# SlimTx.net
KiCad netlist of a schematic drawn in Altium Designer
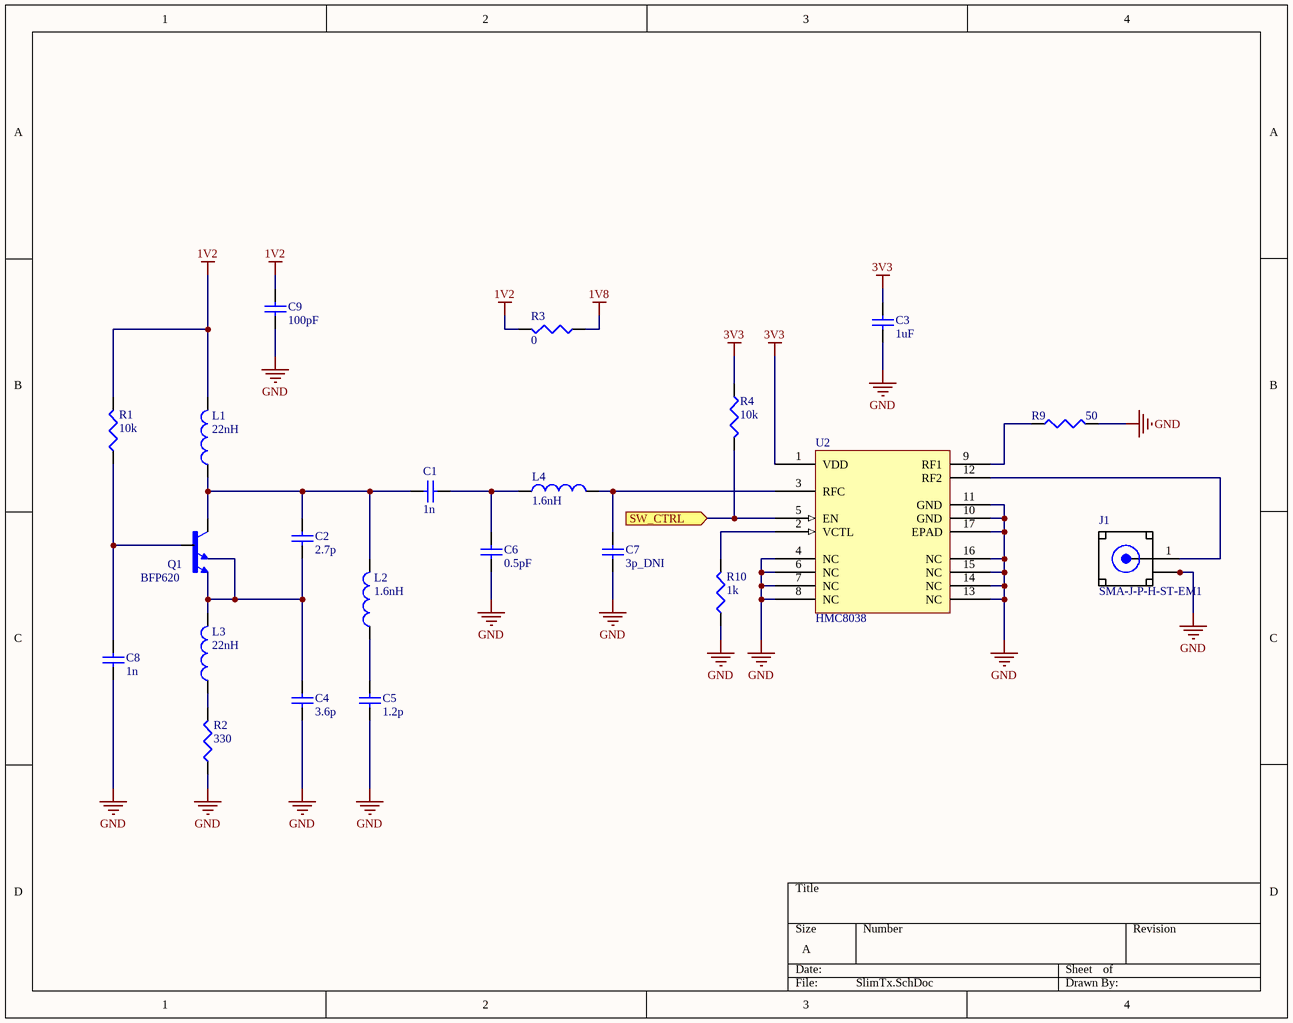
[diagram p0: SlimTx.SchDoc]

(export (version "E")
  (design (tool "Eeschema 10.0.6"))
  (components
    (comp (ref "C1")
      (value "1n")
      (footprint "SMD-0603")
      (description "Ceramic Capacitor 0603")
      (libsource (lib "LCR") (part "CAP0603"))
    )
    (comp (ref "C2")
      (value "2.7p")
      (footprint "SMD-0603")
      (description "Ceramic Capacitor 0603")
      (libsource (lib "LCR") (part "CAP0603"))
    )
    (comp (ref "C3")
      (value "1uF")
      (footprint "SMD-0603")
      (description "Ceramic Capacitor 0603")
      (libsource (lib "LCR") (part "CAP0603"))
    )
    (comp (ref "C4")
      (value "3.6p")
      (footprint "SMD-0603")
      (description "Ceramic Capacitor 0603")
      (libsource (lib "LCR") (part "CAP0603"))
    )
    (comp (ref "C5")
      (value "1.2p")
      (footprint "SMD-0603")
      (description "Ceramic Capacitor 0603")
      (libsource (lib "LCR") (part "CAP0603"))
    )
    (comp (ref "C6")
      (value "0.5pF")
      (footprint "SMD-0603")
      (description "Ceramic Capacitor 0603")
      (libsource (lib "LCR") (part "CAP0603"))
    )
    (comp (ref "C7")
      (value "3p_DNI")
      (footprint "SMD-0603")
      (description "Ceramic Capacitor 0603")
      (libsource (lib "LCR") (part "CAP0603"))
    )
    (comp (ref "C8")
      (value "1n")
      (footprint "SMD-0603")
      (description "Ceramic Capacitor 0603")
      (libsource (lib "LCR") (part "CAP0603"))
    )
    (comp (ref "C9")
      (value "100pF")
      (footprint "SMD-0603")
      (description "Ceramic Capacitor 0603")
      (libsource (lib "LCR") (part "CAP0603"))
    )
    (comp (ref "J1")
      (value "SMA-J-P-H-ST-EM1")
      (footprint "SMA-J-P-H-ST-EM1")
      (description "Connector SMA F 50Ohm Solder ST Edge Mount Gold Over Nickel Tray")
      (fields (field (name "MF") "Samtec"))
      (libsource (lib "Connectors") (part "SMA-J-P-H-ST-EM1"))
    )
    (comp (ref "L1")
      (value "22nH")
      (footprint "SMD-0603")
      (description "Inductor 0603")
      (libsource (lib "LCR") (part "L0603"))
    )
    (comp (ref "L2")
      (value "1.6nH")
      (footprint "SMD-0603")
      (description "Inductor 0603")
      (libsource (lib "LCR") (part "L0603"))
    )
    (comp (ref "L3")
      (value "22nH")
      (footprint "SMD-0603")
      (description "Inductor 0603")
      (libsource (lib "LCR") (part "L0603"))
    )
    (comp (ref "L4")
      (value "1.6nH")
      (footprint "SMD-0603")
      (description "Inductor 0603")
      (libsource (lib "LCR") (part "L0603"))
    )
    (comp (ref "Q1")
      (value "BFP620")
      (footprint "SOT343")
      (description "Trans RF BJT NPN 2.3V 0.08A 185mW Automotive 4-Pin(3+Tab) SOT-343 T/R")
      (fields (field (name "MF") "Infineon Technologies"))
      (libsource (lib "BFP620") (part "BFP620"))
    )
    (comp (ref "R1")
      (value "10k")
      (footprint "SMD-0603")
      (description "Resistor-0603")
      (libsource (lib "LCR") (part "RES0603"))
    )
    (comp (ref "R2")
      (value "330")
      (footprint "SMD-0603")
      (description "Resistor-0603")
      (libsource (lib "LCR") (part "RES0603"))
    )
    (comp (ref "R3")
      (value "0")
      (footprint "SMD-0603")
      (description "Resistor-0603")
      (libsource (lib "LCR") (part "RES0603"))
    )
    (comp (ref "R4")
      (value "10k")
      (footprint "SMD-0603")
      (description "Resistor-0603")
      (libsource (lib "LCR") (part "RES0603"))
    )
    (comp (ref "R9")
      (value "50")
      (footprint "SMD-0603")
      (description "Resistor-0603")
      (libsource (lib "LCR") (part "RES0603"))
    )
    (comp (ref "R10")
      (value "1k")
      (footprint "SMD-0603")
      (description "Resistor-0603")
      (libsource (lib "LCR") (part "RES0603"))
    )
    (comp (ref "U2")
      (value "HMC8038")
      (footprint "PQFN127P600-8N LFCSP-17")
      (description "High Isolation, Silicon SPDT, Nonreflective Switch, 0.1 GHz to 6.0 GHz")
      (libsource (lib "HMC8038") (part "HMC8038"))
    )
  )
  (nets
    (net (code "1") (name "/SW_CTRL") (class "Default")
      (node (ref "R4") (pin "2") (pinfunction "2_2") (pintype "passive"))
      (node (ref "U2") (pin "5") (pinfunction "EN_5") (pintype "input"))
    )
    (net (code "2") (name "1V2") (class "Default")
      (node (ref "C9") (pin "2") (pinfunction "2_2") (pintype "passive"))
      (node (ref "L1") (pin "2") (pinfunction "2_2") (pintype "passive"))
      (node (ref "R1") (pin "2") (pinfunction "2_2") (pintype "passive"))
      (node (ref "R3") (pin "2") (pinfunction "2_2") (pintype "passive"))
    )
    (net (code "3") (name "1V8") (class "Default")
      (node (ref "R3") (pin "1") (pinfunction "1_1") (pintype "passive"))
    )
    (net (code "4") (name "3V3") (class "Default")
      (node (ref "C3") (pin "2") (pinfunction "2_2") (pintype "passive"))
      (node (ref "R4") (pin "1") (pinfunction "1_1") (pintype "passive"))
      (node (ref "U2") (pin "1") (pinfunction "VDD_1") (pintype "power_in"))
    )
    (net (code "5") (name "GND") (class "Default")
      (node (ref "C3") (pin "1") (pinfunction "1_1") (pintype "passive"))
      (node (ref "C4") (pin "1") (pinfunction "1_1") (pintype "passive"))
      (node (ref "C5") (pin "1") (pinfunction "1_1") (pintype "passive"))
      (node (ref "C6") (pin "1") (pinfunction "1_1") (pintype "passive"))
      (node (ref "C7") (pin "1") (pinfunction "1_1") (pintype "passive"))
      (node (ref "C8") (pin "1") (pinfunction "1_1") (pintype "passive"))
      (node (ref "C9") (pin "1") (pinfunction "1_1") (pintype "passive"))
      (node (ref "J1") (pin "2_1") (pinfunction "GND_2_1") (pintype "power_in"))
      (node (ref "J1") (pin "2_2") (pinfunction "GND_2_2") (pintype "power_in"))
      (node (ref "J1") (pin "3_1") (pinfunction "GND_3_1") (pintype "power_in"))
      (node (ref "J1") (pin "3_2") (pinfunction "GND_3_2") (pintype "power_in"))
      (node (ref "R10") (pin "1") (pinfunction "1_1") (pintype "passive"))
      (node (ref "R2") (pin "1") (pinfunction "1_1") (pintype "passive"))
      (node (ref "R9") (pin "2") (pinfunction "2_2") (pintype "passive"))
      (node (ref "U2") (pin "10") (pinfunction "GND_10") (pintype "power_in"))
      (node (ref "U2") (pin "11") (pinfunction "GND_11") (pintype "power_in"))
      (node (ref "U2") (pin "13") (pinfunction "NC_13") (pintype "passive"))
      (node (ref "U2") (pin "14") (pinfunction "NC_14") (pintype "passive"))
      (node (ref "U2") (pin "15") (pinfunction "NC_15") (pintype "passive"))
      (node (ref "U2") (pin "16") (pinfunction "NC_16") (pintype "passive"))
      (node (ref "U2") (pin "17") (pinfunction "EPAD_17") (pintype "passive"))
      (node (ref "U2") (pin "4") (pinfunction "NC_4") (pintype "passive"))
      (node (ref "U2") (pin "6") (pinfunction "NC_6") (pintype "passive"))
      (node (ref "U2") (pin "7") (pinfunction "NC_7") (pintype "passive"))
      (node (ref "U2") (pin "8") (pinfunction "NC_8") (pintype "passive"))
    )
    (net (code "6") (name "Net-(C1-Pad1)") (class "Default")
      (node (ref "C1") (pin "1") (pinfunction "1_1") (pintype "passive"))
      (node (ref "C6") (pin "2") (pinfunction "2_2") (pintype "passive"))
      (node (ref "L4") (pin "1") (pinfunction "1_1") (pintype "passive"))
    )
    (net (code "7") (name "Net-(C5-Pad2)") (class "Default")
      (node (ref "C5") (pin "2") (pinfunction "2_2") (pintype "passive"))
      (node (ref "L2") (pin "1") (pinfunction "1_1") (pintype "passive"))
    )
    (net (code "8") (name "Net-(J1-SIGNAL)") (class "Default")
      (node (ref "J1") (pin "1") (pinfunction "SIGNAL_1") (pintype "passive"))
      (node (ref "U2") (pin "12") (pinfunction "RF2_12") (pintype "passive"))
    )
    (net (code "9") (name "Net-(L3-Pad1)") (class "Default")
      (node (ref "L3") (pin "1") (pinfunction "1_1") (pintype "passive"))
      (node (ref "R2") (pin "2") (pinfunction "2_2") (pintype "passive"))
    )
    (net (code "10") (name "Net-(Q1-B)") (class "Default")
      (node (ref "C8") (pin "2") (pinfunction "2_2") (pintype "passive"))
      (node (ref "Q1") (pin "1") (pinfunction "B_1") (pintype "passive"))
      (node (ref "R1") (pin "1") (pinfunction "1_1") (pintype "passive"))
    )
    (net (code "11") (name "Net-(Q1-C)") (class "Default")
      (node (ref "C1") (pin "2") (pinfunction "2_2") (pintype "passive"))
      (node (ref "C2") (pin "2") (pinfunction "2_2") (pintype "passive"))
      (node (ref "L1") (pin "1") (pinfunction "1_1") (pintype "passive"))
      (node (ref "L2") (pin "2") (pinfunction "2_2") (pintype "passive"))
      (node (ref "Q1") (pin "3") (pinfunction "C_3") (pintype "passive"))
    )
    (net (code "12") (name "Net-(Q1-E1)") (class "Default")
      (node (ref "C2") (pin "1") (pinfunction "1_1") (pintype "passive"))
      (node (ref "C4") (pin "2") (pinfunction "2_2") (pintype "passive"))
      (node (ref "L3") (pin "2") (pinfunction "2_2") (pintype "passive"))
      (node (ref "Q1") (pin "2") (pinfunction "E1_2") (pintype "passive"))
      (node (ref "Q1") (pin "4") (pinfunction "E2_4") (pintype "passive"))
    )
    (net (code "13") (name "Net-(U2-RF1)") (class "Default")
      (node (ref "R9") (pin "1") (pinfunction "1_1") (pintype "passive"))
      (node (ref "U2") (pin "9") (pinfunction "RF1_9") (pintype "passive"))
    )
    (net (code "14") (name "Net-(U2-RFC)") (class "Default")
      (node (ref "C7") (pin "2") (pinfunction "2_2") (pintype "passive"))
      (node (ref "L4") (pin "2") (pinfunction "2_2") (pintype "passive"))
      (node (ref "U2") (pin "3") (pinfunction "RFC_3") (pintype "passive"))
    )
    (net (code "15") (name "Net-(U2-VCTL)") (class "Default")
      (node (ref "R10") (pin "2") (pinfunction "2_2") (pintype "passive"))
      (node (ref "U2") (pin "2") (pinfunction "VCTL_2") (pintype "input"))
    )
  )
)
